# Isolation.net
KiCad netlist of a schematic drawn in Altium Designer
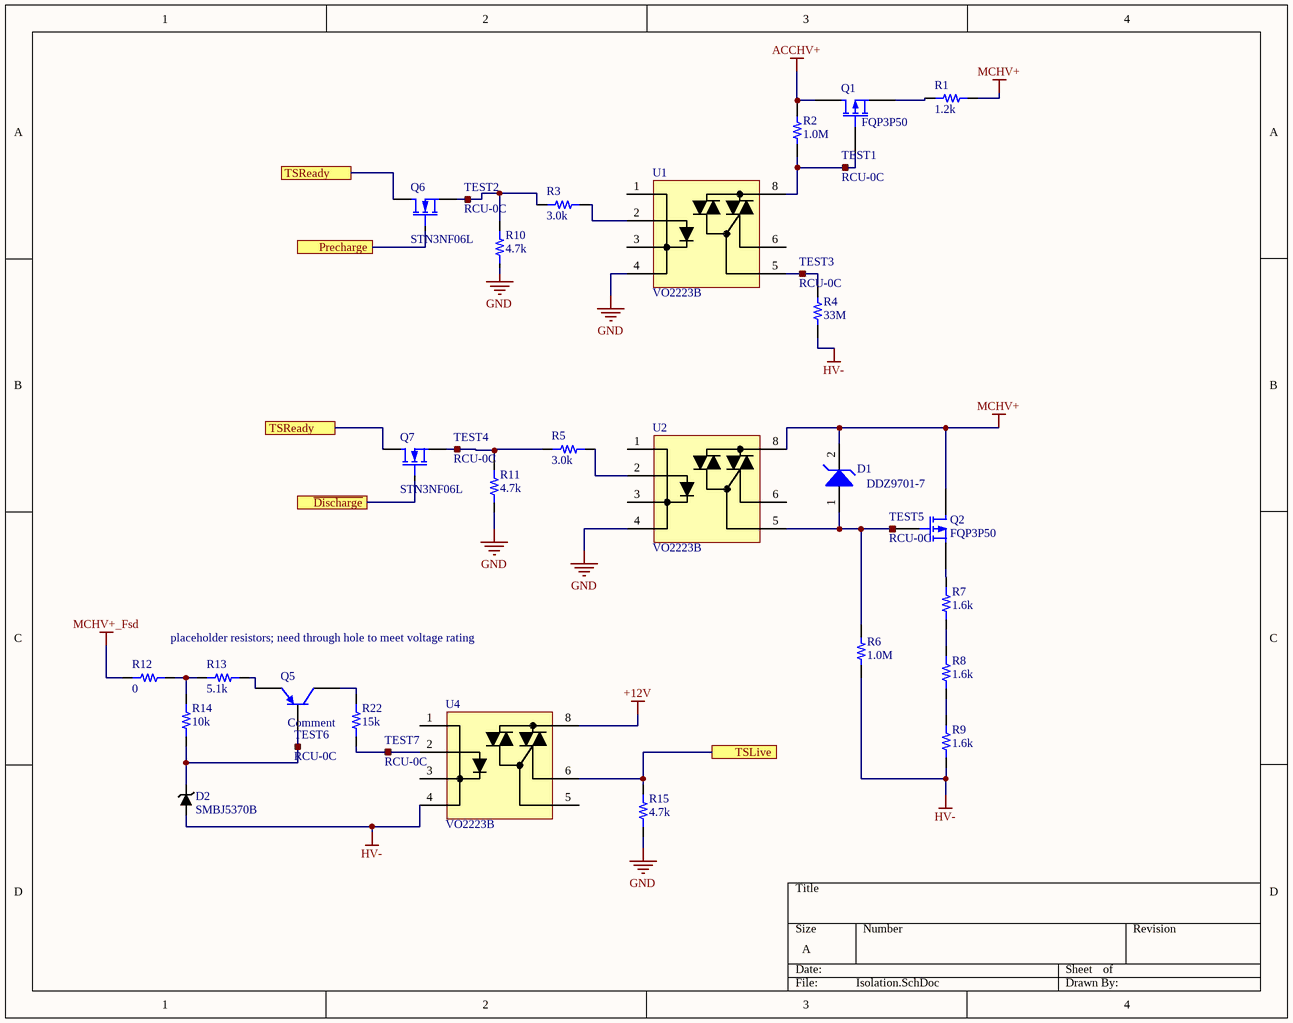
[diagram p0: Isolation.SchDoc]

(export (version "E")
  (design (tool "Eeschema 10.0.6"))
  (components
    (comp (ref "D1")
      (value "DDZ9701-7")
      (footprint "SOD123F")
      (description "Zener Diode 14V 500mW ±5% Surface Mount SOD-123")
      (fields (field (name "POWER") "500mW"))
      (libsource (lib "Altium-Lib") (part "Zener"))
    )
    (comp (ref "D2")
      (value "SMBJ5370B")
      (footprint "SMBJ5370B-TP")
      (description "56V Zener Diode")
      (fields (field (name "CREATED_BY") "Graydon"))
      (libsource (lib "Altium-Lib") (part "SMBJ5370B-TP"))
    )
    (comp (ref "Q1")
      (value "FQP3P50")
      (footprint "TO-220AB")
      (fields (field (name "CREATED_BY") "Angel"))
      (libsource (lib "Altium-Lib") (part "FQP3P50"))
    )
    (comp (ref "Q2")
      (value "FQP3P50")
      (footprint "TO-220AB")
      (fields (field (name "CREATED_BY") "Angel"))
      (libsource (lib "Altium-Lib") (part "FQP3P50"))
    )
    (comp (ref "Q5")
      (value "Comment")
      (footprint "TO-92 (TO-226)")
      (fields (field (name "CREATED_BY") "Angel Delgado"))
      (libsource (lib "Altium-Lib") (part "PNP Transistor"))
    )
    (comp (ref "Q6")
      (value "STN3NF06L")
      (footprint "STN3NF06L")
      (description "MOSFET N-CH 60V 4A SOT223")
      (fields (field (name "CREATED_BY") "Graydon"))
      (libsource (lib "Altium-Lib") (part "STN3NF06L"))
    )
    (comp (ref "Q7")
      (value "STN3NF06L")
      (footprint "STN3NF06L")
      (description "MOSFET N-CH 60V 4A SOT223")
      (fields (field (name "CREATED_BY") "Graydon"))
      (libsource (lib "Altium-Lib") (part "STN3NF06L"))
    )
    (comp (ref "R1")
      (value "1.2k")
      (footprint "AP101")
      (description "100W Throughhole Resistor")
      (fields
        (field (name "TOLERANCE") "5%")
        (field (name "POWER") "100W")
        (field (name "CREATED_BY") "Graydon")
      )
      (libsource (lib "Altium-Lib") (part "Resistor"))
    )
    (comp (ref "R2")
      (value "1.0M")
      (footprint "RES 0603/1608")
      (fields
        (field (name "TOLERANCE") "10%")
        (field (name "POWER") "1/10W")
        (field (name "Comment") "Resistor 1.0M 0603 1/10W 10%")
        (field (name "CREATED_BY") "Nick Mah")
      )
      (libsource (lib "") (part "Resistor_1"))
    )
    (comp (ref "R3")
      (value "3.0k")
      (footprint "RES 0603/1608")
      (fields
        (field (name "TOLERANCE") "1%")
        (field (name "POWER") "1/10W")
        (field (name "Comment") "Resistor 3.0k 0603 1/10W 1%")
        (field (name "CREATED_BY") "Nick Mah")
      )
      (libsource (lib "Altium-Lib") (part "Resistor"))
    )
    (comp (ref "R4")
      (value "33M")
      (footprint "RES 0603/1608")
      (fields
        (field (name "TOLERANCE") "10%")
        (field (name "POWER") "1/10W")
        (field (name "Comment") "Resistor 33M 0603 1/10W 10%")
        (field (name "CREATED_BY") "Nick Mah")
      )
      (libsource (lib "") (part "Resistor_1"))
    )
    (comp (ref "R5")
      (value "3.0k")
      (footprint "RES 0603/1608")
      (fields
        (field (name "TOLERANCE") "1%")
        (field (name "POWER") "1/10W")
        (field (name "Comment") "Resistor 3.0k 0603 1/10W 1%")
        (field (name "CREATED_BY") "Nick Mah")
      )
      (libsource (lib "Altium-Lib") (part "Resistor"))
    )
    (comp (ref "R6")
      (value "1.0M")
      (footprint "RES 0603/1608")
      (fields
        (field (name "TOLERANCE") "1%")
        (field (name "POWER") "1/10W")
        (field (name "Comment") "Resistor 1.0M 0603 1/10W 1%")
        (field (name "CREATED_BY") "Nick Mah")
      )
      (libsource (lib "") (part "Resistor_1"))
    )
    (comp (ref "R7")
      (value "1.6k")
      (footprint "Axial 52mm Pitch")
      (fields
        (field (name "TOLERANCE") "5%")
        (field (name "POWER") "10W")
        (field (name "MFRPARTNO") "SQP10AJB-1K6")
      )
      (libsource (lib "Altium-Lib") (part "Resistor"))
    )
    (comp (ref "R8")
      (value "1.6k")
      (footprint "Axial 52mm Pitch")
      (fields
        (field (name "TOLERANCE") "5%")
        (field (name "POWER") "10W")
        (field (name "MFRPARTNO") "SQP10AJB-1K6")
      )
      (libsource (lib "Altium-Lib") (part "Resistor"))
    )
    (comp (ref "R9")
      (value "1.6k")
      (footprint "Axial 52mm Pitch")
      (fields
        (field (name "TOLERANCE") "5%")
        (field (name "POWER") "10W")
        (field (name "MFRPARTNO") "SQP10AJB-1K6")
      )
      (libsource (lib "Altium-Lib") (part "Resistor"))
    )
    (comp (ref "R10")
      (value "4.7k")
      (footprint "RES 0603/1608")
      (fields
        (field (name "TOLERANCE") "5%")
        (field (name "POWER") "1/10W")
        (field (name "Comment") "Resistor 4.7k 0603 1/10W 5%")
        (field (name "CREATED_BY") "Nick Mah")
      )
      (libsource (lib "Altium-Lib") (part "Resistor"))
    )
    (comp (ref "R11")
      (value "4.7k")
      (footprint "RES 0603/1608")
      (fields
        (field (name "TOLERANCE") "5%")
        (field (name "POWER") "1/10W")
        (field (name "Comment") "Resistor 4.7k 0603 1/10W 5%")
        (field (name "CREATED_BY") "Nick Mah")
      )
      (libsource (lib "Altium-Lib") (part "Resistor"))
    )
    (comp (ref "R12")
      (value "0")
      (footprint "PR02")
      (description "2W TH resistor")
      (fields
        (field (name "TOLERANCE") "5%")
        (field (name "POWER") "2W")
        (field (name "CREATED_BY") "Graydon")
      )
      (libsource (lib "Altium-Lib") (part "Resistor"))
    )
    (comp (ref "R13")
      (value "5.1k")
      (footprint "PR02")
      (description "2W TH resistor")
      (fields
        (field (name "TOLERANCE") "5%")
        (field (name "POWER") "2W")
        (field (name "CREATED_BY") "Graydon")
      )
      (libsource (lib "Altium-Lib") (part "Resistor"))
    )
    (comp (ref "R14")
      (value "10k")
      (footprint "PR02")
      (description "2W TH resistor")
      (fields
        (field (name "TOLERANCE") "5%")
        (field (name "POWER") "2W")
        (field (name "CREATED_BY") "Graydon")
      )
      (libsource (lib "Altium-Lib") (part "Resistor"))
    )
    (comp (ref "R15")
      (value "4.7k")
      (footprint "RES 0603/1608")
      (fields
        (field (name "TOLERANCE") "5%")
        (field (name "POWER") "1/10W")
        (field (name "Comment") "Resistor 4.7k 0603 1/10W 5%")
        (field (name "CREATED_BY") "Nick Mah")
      )
      (libsource (lib "Altium-Lib") (part "Resistor"))
    )
    (comp (ref "R22")
      (value "15k")
      (footprint "PR02")
      (description "2W TH resistor")
      (fields
        (field (name "TOLERANCE") "5%")
        (field (name "POWER") "2W")
        (field (name "CREATED_BY") "Graydon")
      )
      (libsource (lib "Altium-Lib") (part "Resistor"))
    )
    (comp (ref "TEST1")
      (value "RCU-0C")
      (footprint "RCU-0C")
      (description "Test point")
      (fields (field (name "CREATED_BY") "Graydon") (field (name "UPDATED_BY") "Null"))
      (libsource (lib "Altium-Lib") (part "RCU-0C"))
    )
    (comp (ref "TEST2")
      (value "RCU-0C")
      (footprint "RCU-0C")
      (description "Test point")
      (fields (field (name "CREATED_BY") "Graydon") (field (name "UPDATED_BY") "Null"))
      (libsource (lib "Altium-Lib") (part "RCU-0C"))
    )
    (comp (ref "TEST3")
      (value "RCU-0C")
      (footprint "RCU-0C")
      (description "Test point")
      (fields (field (name "CREATED_BY") "Graydon") (field (name "UPDATED_BY") "Null"))
      (libsource (lib "Altium-Lib") (part "RCU-0C"))
    )
    (comp (ref "TEST4")
      (value "RCU-0C")
      (footprint "RCU-0C")
      (description "Test point")
      (fields (field (name "CREATED_BY") "Graydon") (field (name "UPDATED_BY") "Null"))
      (libsource (lib "Altium-Lib") (part "RCU-0C"))
    )
    (comp (ref "TEST5")
      (value "RCU-0C")
      (footprint "RCU-0C")
      (description "Test point")
      (fields (field (name "CREATED_BY") "Graydon") (field (name "UPDATED_BY") "Null"))
      (libsource (lib "Altium-Lib") (part "RCU-0C"))
    )
    (comp (ref "TEST6")
      (value "RCU-0C")
      (footprint "RCU-0C")
      (description "Test point")
      (fields (field (name "CREATED_BY") "Graydon") (field (name "UPDATED_BY") "Null"))
      (libsource (lib "Altium-Lib") (part "RCU-0C"))
    )
    (comp (ref "TEST7")
      (value "RCU-0C")
      (footprint "RCU-0C")
      (description "Test point")
      (fields (field (name "CREATED_BY") "Graydon") (field (name "UPDATED_BY") "Null"))
      (libsource (lib "Altium-Lib") (part "RCU-0C"))
    )
    (comp (ref "U1")
      (value "VO2223B")
      (footprint "Option 7")
      (description "Optocoupler, Power Phototriac")
      (libsource (lib "Altium-Lib") (part "VO2223B"))
    )
    (comp (ref "U2")
      (value "VO2223B")
      (footprint "Option 7")
      (description "Optocoupler, Power Phototriac")
      (libsource (lib "Altium-Lib") (part "VO2223B"))
    )
    (comp (ref "U4")
      (value "VO2223B")
      (footprint "Option 7")
      (description "Optocoupler, Power Phototriac")
      (libsource (lib "Altium-Lib") (part "VO2223B"))
    )
  )
  (nets
    (net (code "1") (name "+12V") (class "Default") (node (ref "U4") (pin "8") (pintype "power_in")))
    (net (code "2") (name "/Discharge") (class "Default")
      (node (ref "Q7") (pin "1") (pinfunction "G_1") (pintype "passive"))
    )
    (net (code "3") (name "/Precharge") (class "Default")
      (node (ref "Q6") (pin "1") (pinfunction "G_1") (pintype "passive"))
    )
    (net (code "4") (name "/TSLive") (class "Default")
      (node (ref "R15") (pin "2") (pinfunction "2_2") (pintype "passive"))
      (node (ref "U4") (pin "6") (pintype "power_in"))
    )
    (net (code "5") (name "/TSReady") (class "Default")
      (node (ref "Q6") (pin "2") (pinfunction "D_2") (pintype "passive"))
      (node (ref "Q7") (pin "2") (pinfunction "D_2") (pintype "passive"))
    )
    (net (code "6") (name "ACCHV+") (class "Default")
      (node (ref "Q1") (pin "2") (pinfunction "D_2") (pintype "passive"))
      (node (ref "R2") (pin "1") (pinfunction "1_1") (pintype "passive"))
    )
    (net (code "7") (name "GND") (class "Default")
      (node (ref "R10") (pin "1") (pinfunction "1_1") (pintype "passive"))
      (node (ref "R11") (pin "1") (pinfunction "1_1") (pintype "passive"))
      (node (ref "R15") (pin "1") (pinfunction "1_1") (pintype "passive"))
      (node (ref "U1") (pin "4") (pintype "power_in"))
      (node (ref "U2") (pin "4") (pintype "power_in"))
    )
    (net (code "8") (name "HV-") (class "Default")
      (node (ref "D2") (pin "1") (pintype "power_in"))
      (node (ref "R4") (pin "1") (pinfunction "1_1") (pintype "passive"))
      (node (ref "R6") (pin "1") (pinfunction "1_1") (pintype "passive"))
      (node (ref "R9") (pin "1") (pinfunction "1_1") (pintype "passive"))
      (node (ref "U4") (pin "4") (pintype "power_in"))
    )
    (net (code "9") (name "MCHV+") (class "Default")
      (node (ref "D1") (pin "2") (pinfunction "K_2") (pintype "passive"))
      (node (ref "Q2") (pin "2") (pinfunction "D_2") (pintype "passive"))
      (node (ref "R1") (pin "2") (pinfunction "2_2") (pintype "passive"))
      (node (ref "U2") (pin "8") (pintype "power_in"))
    )
    (net (code "10") (name "MCHV+_Fsd") (class "Default")
      (node (ref "R12") (pin "1") (pinfunction "1_1") (pintype "passive"))
    )
    (net (code "11") (name "Net-(D1-A)") (class "Default")
      (node (ref "D1") (pin "1") (pinfunction "A_1") (pintype "passive"))
      (node (ref "Q2") (pin "1") (pinfunction "G_1") (pintype "passive"))
      (node (ref "R6") (pin "2") (pinfunction "2_2") (pintype "passive"))
      (node (ref "TEST5") (pin "1") (pintype "passive"))
      (node (ref "U2") (pin "5") (pintype "power_in"))
    )
    (net (code "12") (name "Net-(Q1-G)") (class "Default")
      (node (ref "Q1") (pin "1") (pinfunction "G_1") (pintype "passive"))
      (node (ref "R2") (pin "2") (pinfunction "2_2") (pintype "passive"))
      (node (ref "TEST1") (pin "1") (pintype "passive"))
      (node (ref "U1") (pin "8") (pintype "power_in"))
    )
    (net (code "13") (name "Net-(Q1-S)") (class "Default")
      (node (ref "Q1") (pin "3") (pinfunction "S_3") (pintype "passive"))
      (node (ref "R1") (pin "1") (pinfunction "1_1") (pintype "passive"))
    )
    (net (code "14") (name "Net-(Q2-S)") (class "Default")
      (node (ref "Q2") (pin "3") (pinfunction "S_3") (pintype "passive"))
      (node (ref "R7") (pin "2") (pinfunction "2_2") (pintype "passive"))
    )
    (net (code "15") (name "Net-(Q5-B)") (class "Default")
      (node (ref "D2") (pin "2") (pintype "power_in"))
      (node (ref "Q5") (pin "1") (pinfunction "B_1") (pintype "passive"))
      (node (ref "R14") (pin "1") (pinfunction "1_1") (pintype "passive"))
      (node (ref "TEST6") (pin "1") (pintype "passive"))
    )
    (net (code "16") (name "Net-(Q5-C)") (class "Default")
      (node (ref "Q5") (pin "3") (pinfunction "C_3") (pintype "passive"))
      (node (ref "R22") (pin "2") (pinfunction "2_2") (pintype "passive"))
    )
    (net (code "17") (name "Net-(Q5-E)") (class "Default")
      (node (ref "Q5") (pin "2") (pinfunction "E_2") (pintype "passive"))
      (node (ref "R13") (pin "2") (pinfunction "2_2") (pintype "passive"))
    )
    (net (code "18") (name "Net-(Q6-S)") (class "Default")
      (node (ref "Q6") (pin "3") (pinfunction "S_3") (pintype "passive"))
      (node (ref "R10") (pin "2") (pinfunction "2_2") (pintype "passive"))
      (node (ref "R3") (pin "1") (pinfunction "1_1") (pintype "passive"))
      (node (ref "TEST2") (pin "1") (pintype "passive"))
    )
    (net (code "19") (name "Net-(Q7-S)") (class "Default")
      (node (ref "Q7") (pin "3") (pinfunction "S_3") (pintype "passive"))
      (node (ref "R11") (pin "2") (pinfunction "2_2") (pintype "passive"))
      (node (ref "R5") (pin "1") (pinfunction "1_1") (pintype "passive"))
      (node (ref "TEST4") (pin "1") (pintype "passive"))
    )
    (net (code "20") (name "Net-(R3-Pad2)") (class "Default")
      (node (ref "R3") (pin "2") (pinfunction "2_2") (pintype "passive"))
      (node (ref "U1") (pin "2") (pintype "power_in"))
    )
    (net (code "21") (name "Net-(R4-Pad2)") (class "Default")
      (node (ref "R4") (pin "2") (pinfunction "2_2") (pintype "passive"))
      (node (ref "TEST3") (pin "1") (pintype "passive"))
      (node (ref "U1") (pin "5") (pintype "power_in"))
    )
    (net (code "22") (name "Net-(R5-Pad2)") (class "Default")
      (node (ref "R5") (pin "2") (pinfunction "2_2") (pintype "passive"))
      (node (ref "U2") (pin "2") (pintype "power_in"))
    )
    (net (code "23") (name "Net-(R7-Pad1)") (class "Default")
      (node (ref "R7") (pin "1") (pinfunction "1_1") (pintype "passive"))
      (node (ref "R8") (pin "2") (pinfunction "2_2") (pintype "passive"))
    )
    (net (code "24") (name "Net-(R8-Pad1)") (class "Default")
      (node (ref "R8") (pin "1") (pinfunction "1_1") (pintype "passive"))
      (node (ref "R9") (pin "2") (pinfunction "2_2") (pintype "passive"))
    )
    (net (code "25") (name "Net-(R12-Pad2)") (class "Default")
      (node (ref "R12") (pin "2") (pinfunction "2_2") (pintype "passive"))
      (node (ref "R13") (pin "1") (pinfunction "1_1") (pintype "passive"))
      (node (ref "R14") (pin "2") (pinfunction "2_2") (pintype "passive"))
    )
    (net (code "26") (name "Net-(R22-Pad1)") (class "Default")
      (node (ref "R22") (pin "1") (pinfunction "1_1") (pintype "passive"))
      (node (ref "TEST7") (pin "1") (pintype "passive"))
      (node (ref "U4") (pin "2") (pintype "power_in"))
    )
    (net (code "27") (name "unconnected-(U1-Pad1)") (class "Default")
      (node (ref "U1") (pin "1") (pintype "power_in"))
    )
    (net (code "28") (name "unconnected-(U1-Pad3)") (class "Default")
      (node (ref "U1") (pin "3") (pintype "power_in"))
    )
    (net (code "29") (name "unconnected-(U1-Pad6)") (class "Default")
      (node (ref "U1") (pin "6") (pintype "power_in"))
    )
    (net (code "30") (name "unconnected-(U2-Pad1)") (class "Default")
      (node (ref "U2") (pin "1") (pintype "power_in"))
    )
    (net (code "31") (name "unconnected-(U2-Pad3)") (class "Default")
      (node (ref "U2") (pin "3") (pintype "power_in"))
    )
    (net (code "32") (name "unconnected-(U2-Pad6)") (class "Default")
      (node (ref "U2") (pin "6") (pintype "power_in"))
    )
    (net (code "33") (name "unconnected-(U4-Pad1)") (class "Default")
      (node (ref "U4") (pin "1") (pintype "power_in"))
    )
    (net (code "34") (name "unconnected-(U4-Pad3)") (class "Default")
      (node (ref "U4") (pin "3") (pintype "power_in"))
    )
    (net (code "35") (name "unconnected-(U4-Pad5)") (class "Default")
      (node (ref "U4") (pin "5") (pintype "power_in"))
    )
  )
)
